# Sheet1.net
KiCad netlist of a schematic drawn in Altium Designer
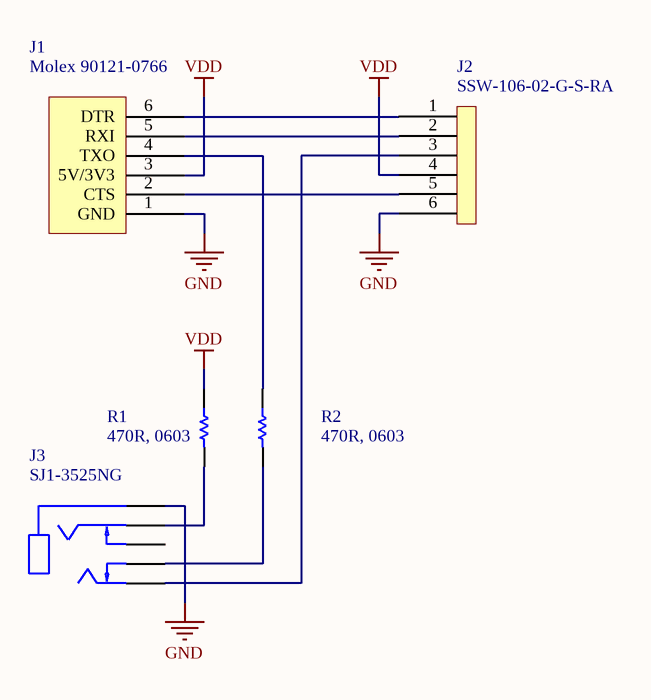
[diagram p0: Sheet1.SchDoc]

(export (version "E")
  (design (tool "Eeschema 10.0.6"))
  (components
    (comp (ref "J1")
      (value "Molex 90121-0766")
      (footprint "FTDI Breakout with Molex 90121-0766")
      (libsource (lib "x-io") (part "FTDI Breakout"))
    )
    (comp (ref "J2")
      (value "SSW-106-02-G-S-RA")
      (footprint "SSW-106-02-G-S-RA")
      (libsource (lib "x-io") (part "SSW-106-02-G-S-RA"))
    )
    (comp (ref "J3")
      (value "SJ1-3525NG")
      (footprint "SJ1-3525NG")
      (libsource (lib "x-io") (part "SJ1-3525NG"))
    )
    (comp (ref "R1")
      (value "470R, 0603")
      (footprint "Resistor 0603")
      (libsource (lib "x-io") (part "Resistor"))
    )
    (comp (ref "R2")
      (value "470R, 0603")
      (footprint "Resistor 0603")
      (libsource (lib "x-io") (part "Resistor"))
    )
  )
  (nets
    (net (code "1") (name "GND") (class "Default")
      (node (ref "J1") (pin "1") (pinfunction "GND_1") (pintype "passive"))
      (node (ref "J2") (pin "6") (pinfunction "6_6") (pintype "passive"))
      (node (ref "J3") (pin "1") (pinfunction "sleeve_1") (pintype "passive"))
    )
    (net (code "2") (name "Net-(J1-CTS)") (class "Default")
      (node (ref "J1") (pin "2") (pinfunction "CTS_2") (pintype "passive"))
      (node (ref "J2") (pin "5") (pinfunction "5_5") (pintype "passive"))
    )
    (net (code "3") (name "Net-(J1-DTR)") (class "Default")
      (node (ref "J1") (pin "6") (pinfunction "DTR_6") (pintype "passive"))
      (node (ref "J2") (pin "1") (pinfunction "1_1") (pintype "passive"))
    )
    (net (code "4") (name "Net-(J1-RXI)") (class "Default")
      (node (ref "J1") (pin "5") (pinfunction "RXI_5") (pintype "passive"))
      (node (ref "J2") (pin "2") (pinfunction "2_2") (pintype "passive"))
    )
    (net (code "5") (name "Net-(J1-TXO)") (class "Default")
      (node (ref "J1") (pin "4") (pinfunction "TXO_4") (pintype "passive"))
      (node (ref "R2") (pin "2") (pinfunction "2_2") (pintype "passive"))
    )
    (net (code "6") (name "Net-(J3-ring)") (class "Default")
      (node (ref "J3") (pin "3") (pinfunction "ring_3") (pintype "passive"))
      (node (ref "R1") (pin "1") (pinfunction "1_1") (pintype "passive"))
    )
    (net (code "7") (name "Net-(J3-tip)") (class "Default")
      (node (ref "J2") (pin "3") (pinfunction "3_3") (pintype "passive"))
      (node (ref "J3") (pin "2") (pinfunction "tip_2") (pintype "passive"))
    )
    (net (code "8") (name "Net-(J3-tip_switch)") (class "Default")
      (node (ref "J3") (pin "4") (pinfunction "tip_switch_4") (pintype "passive"))
      (node (ref "R2") (pin "1") (pinfunction "1_1") (pintype "passive"))
    )
    (net (code "9") (name "VDD") (class "Default")
      (node (ref "J1") (pin "3") (pinfunction "5V/3V3_3") (pintype "passive"))
      (node (ref "J2") (pin "4") (pinfunction "4_4") (pintype "passive"))
      (node (ref "R1") (pin "2") (pinfunction "2_2") (pintype "passive"))
    )
    (net (code "10") (name "unconnected-(J3-ring_switch-Pad5)") (class "Default")
      (node (ref "J3") (pin "5") (pinfunction "ring_switch_5") (pintype "passive"))
    )
  )
)
